# 09-USBUart_PPSMUX_UARTMUX.net
KiCad netlist of a schematic drawn in Altium Designer
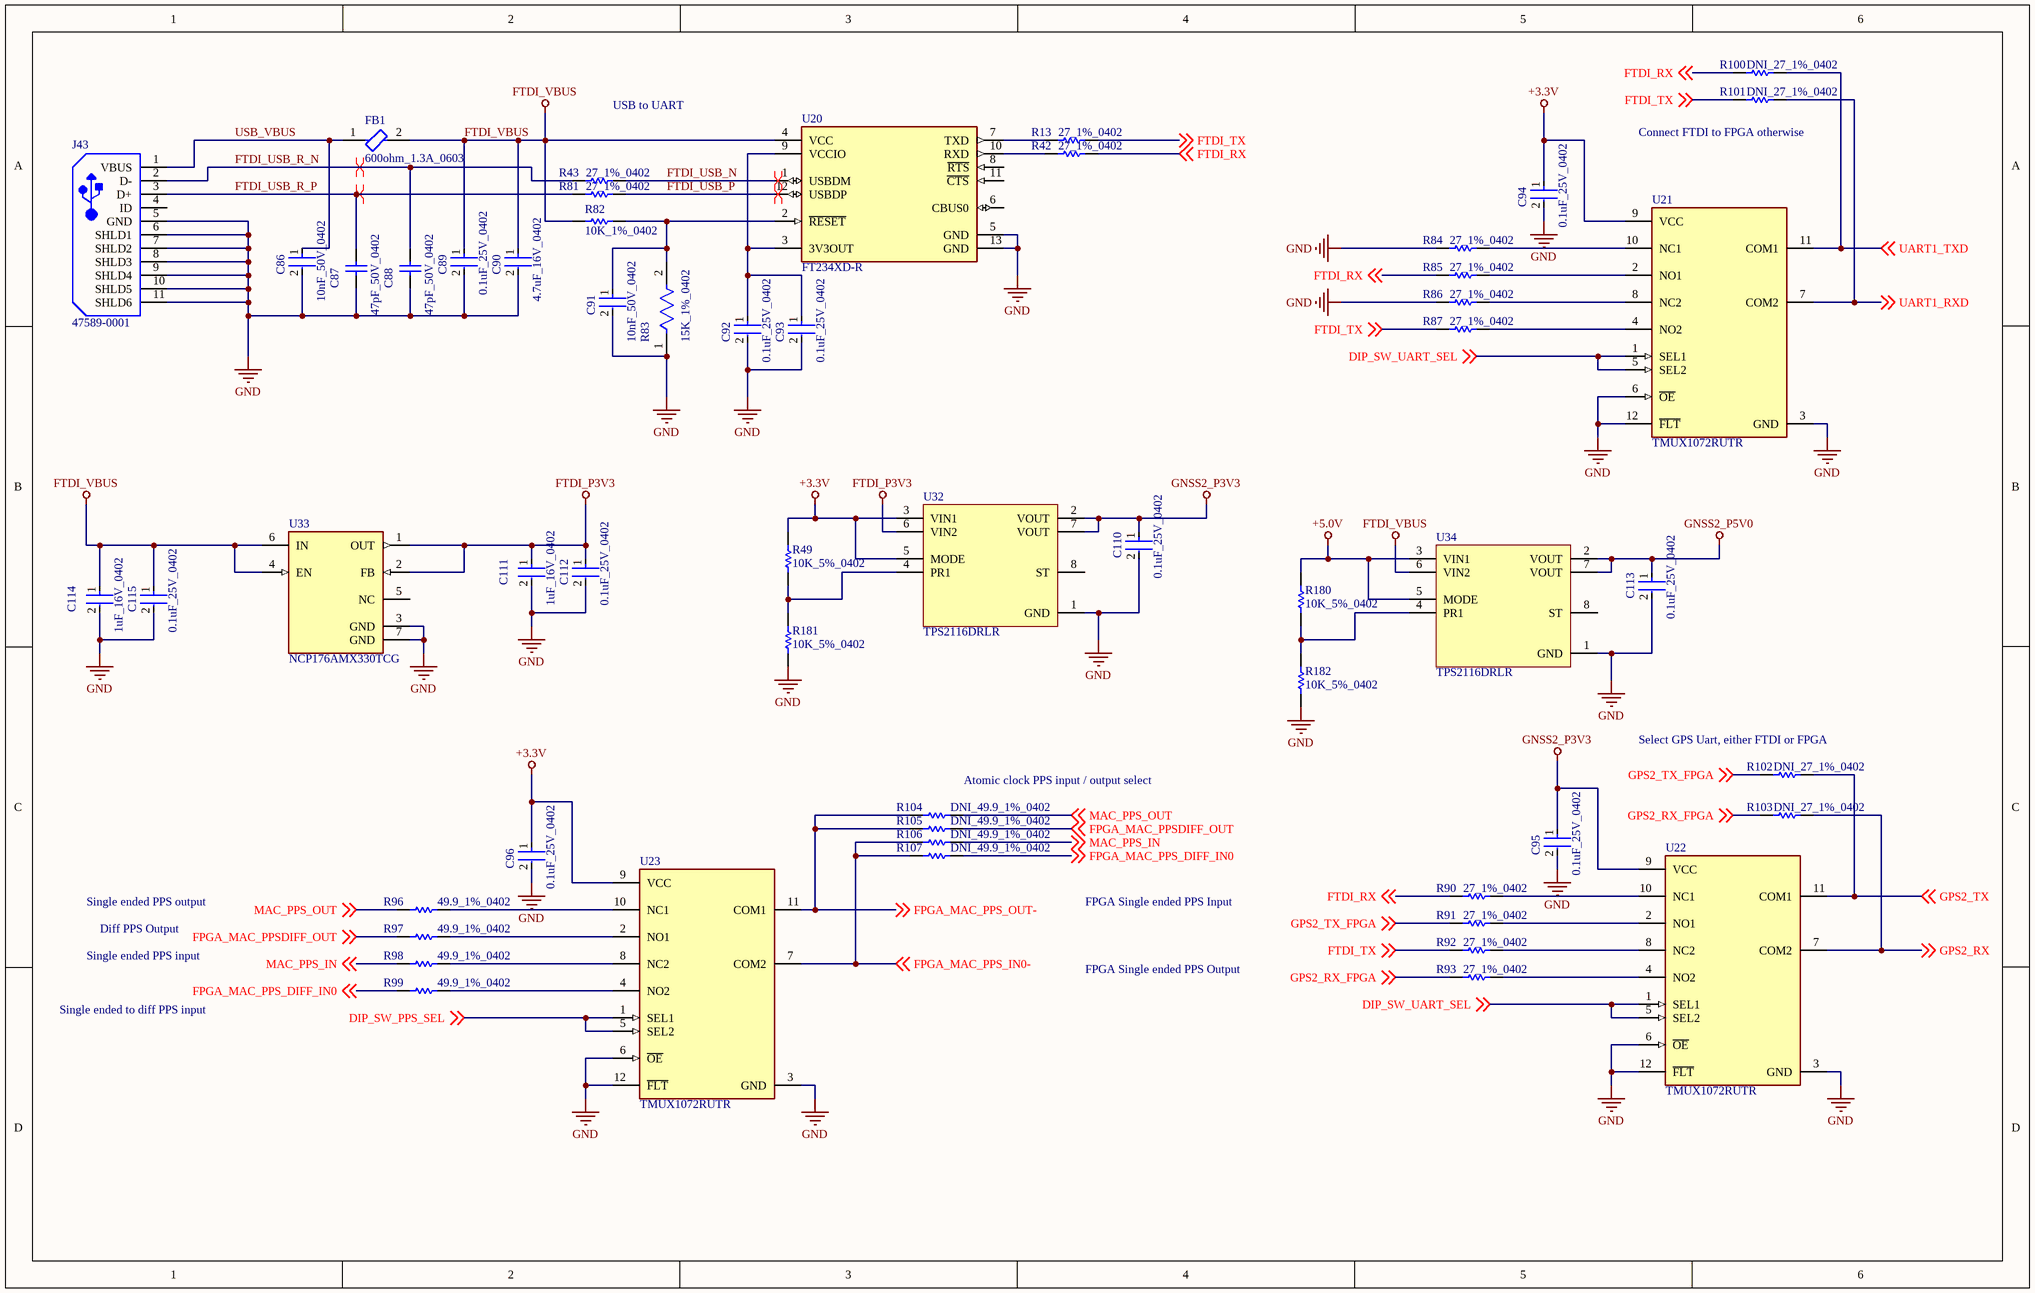
[diagram p0: 09-USBUart_PPSMUX_UARTMUX.SchDoc]

(export (version "E")
  (design (tool "Eeschema 10.0.6"))
  (components
    (comp (ref "C86")
      (value "10nF_50V_0402")
      (footprint "FP-CC0402-MFG")
      (description "CAP CER 10000PF 50V X7R 0402")
      (fields
        (field (name "OCTOPART") "https://octopart.com/cc0402krx7r9bb103-yageo-8376513")
        (field (name "MANUFACTURER PART NUMBER") "CC0402KRX7R9BB103")
      )
      (libsource (lib "Altium Content Vault") (part "11868f565c42a9108669ba33697ecf6"))
    )
    (comp (ref "C87")
      (value "47pF_50V_0402")
      (footprint "CAPC1005X55X25LL05T10")
      (fields (field (name "PART NUMBER") "GRM1555C1H470JA01D") (field (name "MANUFACTURER") "Murata"))
      (libsource (lib "Altium Content Vault") (part "CAP"))
    )
    (comp (ref "C88")
      (value "47pF_50V_0402")
      (footprint "CAPC1005X55X25LL05T10")
      (fields (field (name "PART NUMBER") "GRM1555C1H470JA01D") (field (name "MANUFACTURER") "Murata"))
      (libsource (lib "Altium Content Vault") (part "CAP"))
    )
    (comp (ref "C89")
      (value "0.1uF_25V_0402")
      (footprint "FP-0402-L_1_0_1-W_0_5_0_1-IPC_C")
      (description "General Purpose Ceramic Capacitor, 0402, 100nF, 10%, X7R, 15%, 25V")
      (fields (field (name "VOLTAGE") "25V") (field (name "TOLERANCE") "10%"))
      (libsource (lib "Altium Content Vault") (part "b4654b650e69147ec39a6b967a45e02"))
    )
    (comp (ref "C90")
      (value "4.7uF_16V_0402")
      (footprint "FP-CL829-IPC_C")
      (description "Cap Ceramic 4.7uF 16V X5R ±20% SMD 0402 +85°C Paper T/R")
      (fields (field (name "TOLERANCE") "20%"))
      (libsource (lib "Altium Content Vault") (part "b4654b650e69147ec39a6b967a45e02"))
    )
    (comp (ref "C91")
      (value "10nF_50V_0402")
      (footprint "FP-CC0402-MFG")
      (description "CAP CER 10000PF 50V X7R 0402")
      (fields
        (field (name "OCTOPART") "https://octopart.com/cc0402krx7r9bb103-yageo-8376513")
        (field (name "MANUFACTURER PART NUMBER") "CC0402KRX7R9BB103")
      )
      (libsource (lib "Altium Content Vault") (part "11868f565c42a9108669ba33697ecf6"))
    )
    (comp (ref "C92")
      (value "0.1uF_25V_0402")
      (footprint "FP-0402-L_1_0_1-W_0_5_0_1-IPC_C")
      (description "General Purpose Ceramic Capacitor, 0402, 100nF, 10%, X7R, 15%, 25V")
      (fields (field (name "VOLTAGE") "25V") (field (name "TOLERANCE") "10%"))
      (libsource (lib "Altium Content Vault") (part "b4654b650e69147ec39a6b967a45e02"))
    )
    (comp (ref "C93")
      (value "0.1uF_25V_0402")
      (footprint "FP-0402-L_1_0_1-W_0_5_0_1-IPC_C")
      (description "General Purpose Ceramic Capacitor, 0402, 100nF, 10%, X7R, 15%, 25V")
      (fields (field (name "VOLTAGE") "25V") (field (name "TOLERANCE") "10%"))
      (libsource (lib "Altium Content Vault") (part "b4654b650e69147ec39a6b967a45e02"))
    )
    (comp (ref "C94")
      (value "0.1uF_25V_0402")
      (footprint "FP-0402-L_1_0_1-W_0_5_0_1-IPC_C")
      (description "General Purpose Ceramic Capacitor, 0402, 100nF, 10%, X7R, 15%, 25V")
      (fields (field (name "VOLTAGE") "25V") (field (name "TOLERANCE") "10%"))
      (libsource (lib "Altium Content Vault") (part "b4654b650e69147ec39a6b967a45e02"))
    )
    (comp (ref "C95")
      (value "0.1uF_25V_0402")
      (footprint "FP-0402-L_1_0_1-W_0_5_0_1-IPC_C")
      (description "General Purpose Ceramic Capacitor, 0402, 100nF, 10%, X7R, 15%, 25V")
      (fields (field (name "VOLTAGE") "25V") (field (name "TOLERANCE") "10%"))
      (libsource (lib "Altium Content Vault") (part "b4654b650e69147ec39a6b967a45e02"))
    )
    (comp (ref "C96")
      (value "0.1uF_25V_0402")
      (footprint "FP-0402-L_1_0_1-W_0_5_0_1-IPC_C")
      (description "General Purpose Ceramic Capacitor, 0402, 100nF, 10%, X7R, 15%, 25V")
      (fields (field (name "VOLTAGE") "25V") (field (name "TOLERANCE") "10%"))
      (libsource (lib "Altium Content Vault") (part "b4654b650e69147ec39a6b967a45e02"))
    )
    (comp (ref "C110")
      (value "0.1uF_25V_0402")
      (footprint "FP-0402-L_1_0_1-W_0_5_0_1-IPC_C")
      (description "General Purpose Ceramic Capacitor, 0402, 100nF, 10%, X7R, 15%, 25V")
      (fields (field (name "VOLTAGE") "25V") (field (name "TOLERANCE") "10%"))
      (libsource (lib "Altium Content Vault") (part "b4654b650e69147ec39a6b967a45e02"))
    )
    (comp (ref "C111")
      (value "1uF_16V_0402")
      (footprint "FP-0402-L_1_0_0_05-W_0_5-IPC_A")
      (description "None")
      (fields (field (name "TOLERANCE") "10%"))
      (libsource (lib "Altium Content Vault") (part "b4654b650e69147ec39a6b967a45e02"))
    )
    (comp (ref "C112")
      (value "0.1uF_25V_0402")
      (footprint "FP-0402-L_1_0_1-W_0_5_0_1-IPC_C")
      (description "General Purpose Ceramic Capacitor, 0402, 100nF, 10%, X7R, 15%, 25V")
      (fields (field (name "VOLTAGE") "25V") (field (name "TOLERANCE") "10%"))
      (libsource (lib "Altium Content Vault") (part "b4654b650e69147ec39a6b967a45e02"))
    )
    (comp (ref "C113")
      (value "0.1uF_25V_0402")
      (footprint "FP-0402-L_1_0_1-W_0_5_0_1-IPC_C")
      (description "General Purpose Ceramic Capacitor, 0402, 100nF, 10%, X7R, 15%, 25V")
      (fields (field (name "VOLTAGE") "25V") (field (name "TOLERANCE") "10%"))
      (libsource (lib "Altium Content Vault") (part "b4654b650e69147ec39a6b967a45e02"))
    )
    (comp (ref "C114")
      (value "1uF_16V_0402")
      (footprint "FP-0402-L_1_0_0_05-W_0_5-IPC_A")
      (description "None")
      (fields (field (name "TOLERANCE") "10%"))
      (libsource (lib "Altium Content Vault") (part "b4654b650e69147ec39a6b967a45e02"))
    )
    (comp (ref "C115")
      (value "0.1uF_25V_0402")
      (footprint "FP-0402-L_1_0_1-W_0_5_0_1-IPC_C")
      (description "General Purpose Ceramic Capacitor, 0402, 100nF, 10%, X7R, 15%, 25V")
      (fields (field (name "VOLTAGE") "25V") (field (name "TOLERANCE") "10%"))
      (libsource (lib "Altium Content Vault") (part "b4654b650e69147ec39a6b967a45e02"))
    )
    (comp (ref "FB1")
      (value "600ohm_1.3A_0603")
      (footprint "FP-BLM18-0_15-t0_8-IPC_A")
      (description "Chip Ferrite Bead, 0603, 600Ω @ 100MHz, 0.15Ω, 25%, 1.3A")
      (fields (field (name "TOLERANCE") "25%"))
      (libsource (lib "Altium Content Vault") (part "5f30dd21d616792df468990f7003faa"))
    )
    (comp (ref "J43")
      (value "47589-0001")
      (footprint "MOLX-47589-0001_V")
      (description "Right Angle Female Type AB Micro USB Connector, 30 V, 1.8 A, -30 to 85 degC, RoHS, Tape and Reel")
      (fields (field (name "MANUFACTURER") "Molex"))
      (libsource (lib "Altium Content Vault") (part "USB-5-6SHLD"))
    )
    (comp (ref "R13")
      (value "27_1%_0402")
      (footprint "RESC1005X40X25NL05T05")
      (fields (field (name "PART NUMBER") "CRCW040227R0FKED") (field (name "MANUFACTURER") "Vishay Dale"))
      (libsource (lib "Altium Content Vault") (part "RES"))
    )
    (comp (ref "R42")
      (value "27_1%_0402")
      (footprint "RESC1005X40X25NL05T05")
      (fields (field (name "PART NUMBER") "CRCW040227R0FKED") (field (name "MANUFACTURER") "Vishay Dale"))
      (libsource (lib "Altium Content Vault") (part "RES"))
    )
    (comp (ref "R43")
      (value "27_1%_0402")
      (footprint "RESC1005X40X25NL05T05")
      (fields (field (name "PART NUMBER") "CRCW040227R0FKED") (field (name "MANUFACTURER") "Vishay Dale"))
      (libsource (lib "Altium Content Vault") (part "RES"))
    )
    (comp (ref "R49")
      (value "10K_5%_0402")
      (footprint "RESC1005X40X25ML05T05")
      (fields (field (name "PART NUMBER") "ERJ-2GEJ103X") (field (name "MANUFACTURER") "Panasonic"))
      (libsource (lib "Altium Content Vault") (part "RES"))
    )
    (comp (ref "R81")
      (value "27_1%_0402")
      (footprint "RESC1005X40X25NL05T05")
      (fields (field (name "PART NUMBER") "CRCW040227R0FKED") (field (name "MANUFACTURER") "Vishay Dale"))
      (libsource (lib "Altium Content Vault") (part "RES"))
    )
    (comp (ref "R82")
      (value "10K_1%_0402")
      (footprint "RESC1005X40X25LL05T10")
      (fields (field (name "PART NUMBER") "RC0402FR-0710KL") (field (name "MANUFACTURER") "Yageo / Phycomp"))
      (libsource (lib "Altium Content Vault") (part "RES"))
    )
    (comp (ref "R83")
      (value "15K_1%_0402")
      (footprint "FP-ERJ2R-MFG")
      (description "RES SMD 15K OHM 1% 1/10W 0402")
      (fields (field (name "TOLERANCE") "1%") (field (name "MANUFACTURER PART NUMBER") "ERJ-2RKF1502X"))
      (libsource (lib "Altium Content Vault") (part "1029c3af85768c4190bb7ad29bc67b5"))
    )
    (comp (ref "R84")
      (value "27_1%_0402")
      (footprint "RESC1005X40X25NL05T05")
      (fields (field (name "PART NUMBER") "CRCW040227R0FKED") (field (name "MANUFACTURER") "Vishay Dale"))
      (libsource (lib "Altium Content Vault") (part "RES"))
    )
    (comp (ref "R85")
      (value "27_1%_0402")
      (footprint "RESC1005X40X25NL05T05")
      (fields (field (name "PART NUMBER") "CRCW040227R0FKED") (field (name "MANUFACTURER") "Vishay Dale"))
      (libsource (lib "Altium Content Vault") (part "RES"))
    )
    (comp (ref "R86")
      (value "27_1%_0402")
      (footprint "RESC1005X40X25NL05T05")
      (fields (field (name "PART NUMBER") "CRCW040227R0FKED") (field (name "MANUFACTURER") "Vishay Dale"))
      (libsource (lib "Altium Content Vault") (part "RES"))
    )
    (comp (ref "R87")
      (value "27_1%_0402")
      (footprint "RESC1005X40X25NL05T05")
      (fields (field (name "PART NUMBER") "CRCW040227R0FKED") (field (name "MANUFACTURER") "Vishay Dale"))
      (libsource (lib "Altium Content Vault") (part "RES"))
    )
    (comp (ref "R90")
      (value "27_1%_0402")
      (footprint "RESC1005X40X25NL05T05")
      (fields (field (name "PART NUMBER") "CRCW040227R0FKED") (field (name "MANUFACTURER") "Vishay Dale"))
      (libsource (lib "Altium Content Vault") (part "RES"))
    )
    (comp (ref "R91")
      (value "27_1%_0402")
      (footprint "RESC1005X40X25NL05T05")
      (fields (field (name "PART NUMBER") "CRCW040227R0FKED") (field (name "MANUFACTURER") "Vishay Dale"))
      (libsource (lib "Altium Content Vault") (part "RES"))
    )
    (comp (ref "R92")
      (value "27_1%_0402")
      (footprint "RESC1005X40X25NL05T05")
      (fields (field (name "PART NUMBER") "CRCW040227R0FKED") (field (name "MANUFACTURER") "Vishay Dale"))
      (libsource (lib "Altium Content Vault") (part "RES"))
    )
    (comp (ref "R93")
      (value "27_1%_0402")
      (footprint "RESC1005X40X25NL05T05")
      (fields (field (name "PART NUMBER") "CRCW040227R0FKED") (field (name "MANUFACTURER") "Vishay Dale"))
      (libsource (lib "Altium Content Vault") (part "RES"))
    )
    (comp (ref "R96")
      (value "49.9_1%_0402")
      (footprint "RESC1005X40X25LL05T10")
      (fields (field (name "MANUFACTURER") "Yageo / Phycomp") (field (name "PART NUMBER") "RC0402FR-0749R9L"))
      (libsource (lib "Altium Content Vault") (part "RES"))
    )
    (comp (ref "R97")
      (value "49.9_1%_0402")
      (footprint "RESC1005X40X25LL05T10")
      (fields (field (name "MANUFACTURER") "Yageo / Phycomp") (field (name "PART NUMBER") "RC0402FR-0749R9L"))
      (libsource (lib "Altium Content Vault") (part "RES"))
    )
    (comp (ref "R98")
      (value "49.9_1%_0402")
      (footprint "RESC1005X40X25LL05T10")
      (fields (field (name "MANUFACTURER") "Yageo / Phycomp") (field (name "PART NUMBER") "RC0402FR-0749R9L"))
      (libsource (lib "Altium Content Vault") (part "RES"))
    )
    (comp (ref "R99")
      (value "49.9_1%_0402")
      (footprint "RESC1005X40X25LL05T10")
      (fields (field (name "MANUFACTURER") "Yageo / Phycomp") (field (name "PART NUMBER") "RC0402FR-0749R9L"))
      (libsource (lib "Altium Content Vault") (part "RES"))
    )
    (comp (ref "R100")
      (value "DNI_27_1%_0402")
      (footprint "RESC1005X40X25NL05T05")
      (fields (field (name "PART NUMBER") "CRCW040227R0FKED") (field (name "MANUFACTURER") "Vishay Dale"))
      (libsource (lib "Altium Content Vault") (part "RES"))
    )
    (comp (ref "R101")
      (value "DNI_27_1%_0402")
      (footprint "RESC1005X40X25NL05T05")
      (fields (field (name "PART NUMBER") "CRCW040227R0FKED") (field (name "MANUFACTURER") "Vishay Dale"))
      (libsource (lib "Altium Content Vault") (part "RES"))
    )
    (comp (ref "R102")
      (value "DNI_27_1%_0402")
      (footprint "RESC1005X40X25NL05T05")
      (fields (field (name "PART NUMBER") "CRCW040227R0FKED") (field (name "MANUFACTURER") "Vishay Dale"))
      (libsource (lib "Altium Content Vault") (part "RES"))
    )
    (comp (ref "R103")
      (value "DNI_27_1%_0402")
      (footprint "RESC1005X40X25NL05T05")
      (fields (field (name "PART NUMBER") "CRCW040227R0FKED") (field (name "MANUFACTURER") "Vishay Dale"))
      (libsource (lib "Altium Content Vault") (part "RES"))
    )
    (comp (ref "R104")
      (value "DNI_49.9_1%_0402")
      (footprint "RESC1005X40X25LL05T10")
      (fields (field (name "MANUFACTURER") "Yageo / Phycomp") (field (name "PART NUMBER") "RC0402FR-0749R9L"))
      (libsource (lib "Altium Content Vault") (part "RES"))
    )
    (comp (ref "R105")
      (value "DNI_49.9_1%_0402")
      (footprint "RESC1005X40X25LL05T10")
      (fields (field (name "MANUFACTURER") "Yageo / Phycomp") (field (name "PART NUMBER") "RC0402FR-0749R9L"))
      (libsource (lib "Altium Content Vault") (part "RES"))
    )
    (comp (ref "R106")
      (value "DNI_49.9_1%_0402")
      (footprint "RESC1005X40X25LL05T10")
      (fields (field (name "MANUFACTURER") "Yageo / Phycomp") (field (name "PART NUMBER") "RC0402FR-0749R9L"))
      (libsource (lib "Altium Content Vault") (part "RES"))
    )
    (comp (ref "R107")
      (value "DNI_49.9_1%_0402")
      (footprint "RESC1005X40X25LL05T10")
      (fields (field (name "MANUFACTURER") "Yageo / Phycomp") (field (name "PART NUMBER") "RC0402FR-0749R9L"))
      (libsource (lib "Altium Content Vault") (part "RES"))
    )
    (comp (ref "R180")
      (value "10K_5%_0402")
      (footprint "RESC1005X40X25ML05T05")
      (fields (field (name "PART NUMBER") "ERJ-2GEJ103X") (field (name "MANUFACTURER") "Panasonic"))
      (libsource (lib "Altium Content Vault") (part "RES"))
    )
    (comp (ref "R181")
      (value "10K_5%_0402")
      (footprint "RESC1005X40X25ML05T05")
      (fields (field (name "PART NUMBER") "ERJ-2GEJ103X") (field (name "MANUFACTURER") "Panasonic"))
      (libsource (lib "Altium Content Vault") (part "RES"))
    )
    (comp (ref "R182")
      (value "10K_5%_0402")
      (footprint "RESC1005X40X25ML05T05")
      (fields (field (name "PART NUMBER") "ERJ-2GEJ103X") (field (name "MANUFACTURER") "Panasonic"))
      (libsource (lib "Altium Content Vault") (part "RES"))
    )
    (comp (ref "U20")
      (value "FT234XD-R")
      (footprint "FP-DFN-12-IPC_B")
      (description "IC USB SERIAL BASIC UART 12DFN")
      (libsource (lib "Altium Content Vault") (part "4bef3367ed9f9051bcb84ab46edda1c"))
    )
    (comp (ref "U21")
      (value "TMUX1072RUTR")
      (footprint "FP-RUT0012A-MFG")
      (description "IC SWITCH SPDT DUAL 12UQFN")
      (libsource (lib "Altium Content Vault") (part "12a319ab100cd6cfe745e35972674f5"))
    )
    (comp (ref "U22")
      (value "TMUX1072RUTR")
      (footprint "FP-RUT0012A-MFG")
      (description "IC SWITCH SPDT DUAL 12UQFN")
      (libsource (lib "Altium Content Vault") (part "12a319ab100cd6cfe745e35972674f5"))
    )
    (comp (ref "U23")
      (value "TMUX1072RUTR")
      (footprint "FP-RUT0012A-MFG")
      (description "IC SWITCH SPDT DUAL 12UQFN")
      (libsource (lib "Altium Content Vault") (part "12a319ab100cd6cfe745e35972674f5"))
    )
    (comp (ref "U32")
      (value "TPS2116DRLR")
      (footprint "IC_TPS2116")
      (description "1.6-V to 5.5-V, 40-mΩ, 2.5-A, low-IQ, priority power multiplexer 8-SOT-5X3 -40 to 125")
      (fields (field (name "MF") "Texas Instruments"))
      (libsource (lib "LotusSound") (part "IC_TPS2116DRLR"))
    )
    (comp (ref "U33")
      (value "NCP176AMX330TCG")
      (footprint "FP-711AT-MFG")
      (description "IC REG LINEAR 3.3V 500MA 6XDFN")
      (fields
        (field (name "MANUFACTURER") "ON Semiconductor")
        (field (name "OCTOPART") "https://octopart.com/ncp176amx330tcg-on+semiconductor-61522616")
      )
      (libsource (lib "Altium Content Vault") (part "a38d0f79c2a9f01c07a7e52882ed186"))
    )
    (comp (ref "U34")
      (value "TPS2116DRLR")
      (footprint "IC_TPS2116")
      (description "1.6-V to 5.5-V, 40-mΩ, 2.5-A, low-IQ, priority power multiplexer 8-SOT-5X3 -40 to 125")
      (fields (field (name "MF") "Texas Instruments"))
      (libsource (lib "LotusSound") (part "IC_TPS2116DRLR"))
    )
  )
  (nets
    (net (code "1") (name "+3.3V") (class "Default")
      (node (ref "C94") (pin "1") (pinfunction "1_1") (pintype "passive"))
      (node (ref "C96") (pin "1") (pinfunction "1_1") (pintype "passive"))
      (node (ref "R49") (pin "2") (pinfunction "2_2") (pintype "passive"))
      (node (ref "U21") (pin "9") (pinfunction "VCC_9") (pintype "power_in"))
      (node (ref "U23") (pin "9") (pinfunction "VCC_9") (pintype "power_in"))
      (node (ref "U32") (pin "3") (pinfunction "VIN1_3") (pintype "passive"))
      (node (ref "U32") (pin "5") (pinfunction "MODE_5") (pintype "passive"))
    )
    (net (code "2") (name "+5.0V") (class "Default")
      (node (ref "R180") (pin "2") (pinfunction "2_2") (pintype "passive"))
      (node (ref "U34") (pin "3") (pinfunction "VIN1_3") (pintype "passive"))
      (node (ref "U34") (pin "5") (pinfunction "MODE_5") (pintype "passive"))
    )
    (net (code "3") (name "/FTDI_USB_N") (class "Default")
      (node (ref "R43") (pin "2") (pinfunction "2_2") (pintype "passive"))
      (node (ref "U20") (pin "1") (pinfunction "USBDM_1") (pintype "bidirectional"))
    )
    (net (code "4") (name "/FTDI_USB_P") (class "Default")
      (node (ref "R81") (pin "2") (pinfunction "2_2") (pintype "passive"))
      (node (ref "U20") (pin "12") (pinfunction "USBDP_12") (pintype "bidirectional"))
    )
    (net (code "5") (name "/FTDI_USB_R_N") (class "Default")
      (node (ref "C88") (pin "2") (pinfunction "2_2") (pintype "passive"))
      (node (ref "J43") (pin "2") (pinfunction "D-_2") (pintype "passive"))
      (node (ref "R43") (pin "1") (pinfunction "1_1") (pintype "passive"))
    )
    (net (code "6") (name "/FTDI_USB_R_P") (class "Default")
      (node (ref "C87") (pin "2") (pinfunction "2_2") (pintype "passive"))
      (node (ref "J43") (pin "3") (pinfunction "D+_3") (pintype "passive"))
      (node (ref "R81") (pin "1") (pinfunction "1_1") (pintype "passive"))
    )
    (net (code "7") (name "/USB_VBUS") (class "Default")
      (node (ref "C86") (pin "1") (pinfunction "1_1") (pintype "passive"))
      (node (ref "FB1") (pin "1") (pinfunction "1_1") (pintype "passive"))
      (node (ref "J43") (pin "1") (pinfunction "VBUS_1") (pintype "passive"))
    )
    (net (code "8") (name "DIP_SW_PPS_SEL") (class "Default")
      (node (ref "U23") (pin "1") (pinfunction "SEL1_1") (pintype "input"))
      (node (ref "U23") (pin "5") (pinfunction "SEL2_5") (pintype "input"))
    )
    (net (code "9") (name "DIP_SW_UART_SEL") (class "Default")
      (node (ref "U21") (pin "1") (pinfunction "SEL1_1") (pintype "input"))
      (node (ref "U21") (pin "5") (pinfunction "SEL2_5") (pintype "input"))
      (node (ref "U22") (pin "1") (pinfunction "SEL1_1") (pintype "input"))
      (node (ref "U22") (pin "5") (pinfunction "SEL2_5") (pintype "input"))
    )
    (net (code "10") (name "FPGA_MAC_PPSDIFF_OUT") (class "Default")
      (node (ref "R105") (pin "2") (pinfunction "2_2") (pintype "passive"))
      (node (ref "R97") (pin "1") (pinfunction "1_1") (pintype "passive"))
    )
    (net (code "11") (name "FPGA_MAC_PPS_DIFF_IN0") (class "Default")
      (node (ref "R107") (pin "2") (pinfunction "2_2") (pintype "passive"))
      (node (ref "R99") (pin "1") (pinfunction "1_1") (pintype "passive"))
    )
    (net (code "12") (name "FPGA_MAC_PPS_IN0-") (class "Default")
      (node (ref "R106") (pin "1") (pinfunction "1_1") (pintype "passive"))
      (node (ref "R107") (pin "1") (pinfunction "1_1") (pintype "passive"))
      (node (ref "U23") (pin "7") (pinfunction "COM2_7") (pintype "passive"))
    )
    (net (code "13") (name "FPGA_MAC_PPS_OUT-") (class "Default")
      (node (ref "R104") (pin "1") (pinfunction "1_1") (pintype "passive"))
      (node (ref "R105") (pin "1") (pinfunction "1_1") (pintype "passive"))
      (node (ref "U23") (pin "11") (pinfunction "COM1_11") (pintype "passive"))
    )
    (net (code "14") (name "FTDI_P3V3") (class "Default")
      (node (ref "C111") (pin "1") (pinfunction "1_1") (pintype "passive"))
      (node (ref "C112") (pin "1") (pinfunction "1_1") (pintype "passive"))
      (node (ref "U32") (pin "6") (pinfunction "VIN2_6") (pintype "passive"))
      (node (ref "U33") (pin "1") (pinfunction "OUT_1") (pintype "output"))
      (node (ref "U33") (pin "2") (pinfunction "FB_2") (pintype "input"))
    )
    (net (code "15") (name "FTDI_RX") (class "Default")
      (node (ref "R100") (pin "1") (pinfunction "1_1") (pintype "passive"))
      (node (ref "R42") (pin "2") (pinfunction "2_2") (pintype "passive"))
      (node (ref "R85") (pin "1") (pinfunction "1_1") (pintype "passive"))
      (node (ref "R90") (pin "1") (pinfunction "1_1") (pintype "passive"))
    )
    (net (code "16") (name "FTDI_TX") (class "Default")
      (node (ref "R101") (pin "1") (pinfunction "1_1") (pintype "passive"))
      (node (ref "R13") (pin "2") (pinfunction "2_2") (pintype "passive"))
      (node (ref "R87") (pin "1") (pinfunction "1_1") (pintype "passive"))
      (node (ref "R92") (pin "1") (pinfunction "1_1") (pintype "passive"))
    )
    (net (code "17") (name "FTDI_VBUS") (class "Default")
      (node (ref "C114") (pin "1") (pinfunction "1_1") (pintype "passive"))
      (node (ref "C115") (pin "1") (pinfunction "1_1") (pintype "passive"))
      (node (ref "C89") (pin "1") (pinfunction "1_1") (pintype "passive"))
      (node (ref "C90") (pin "1") (pinfunction "1_1") (pintype "passive"))
      (node (ref "FB1") (pin "2") (pinfunction "2_2") (pintype "passive"))
      (node (ref "R82") (pin "2") (pinfunction "2_2") (pintype "passive"))
      (node (ref "U20") (pin "4") (pinfunction "VCC_4") (pintype "power_in"))
      (node (ref "U33") (pin "4") (pinfunction "EN_4") (pintype "input"))
      (node (ref "U33") (pin "6") (pinfunction "IN_6") (pintype "power_in"))
      (node (ref "U34") (pin "6") (pinfunction "VIN2_6") (pintype "passive"))
    )
    (net (code "18") (name "GND") (class "Default")
      (node (ref "C110") (pin "2") (pinfunction "2_2") (pintype "passive"))
      (node (ref "C111") (pin "2") (pinfunction "2_2") (pintype "passive"))
      (node (ref "C112") (pin "2") (pinfunction "2_2") (pintype "passive"))
      (node (ref "C113") (pin "2") (pinfunction "2_2") (pintype "passive"))
      (node (ref "C114") (pin "2") (pinfunction "2_2") (pintype "passive"))
      (node (ref "C115") (pin "2") (pinfunction "2_2") (pintype "passive"))
      (node (ref "C86") (pin "2") (pinfunction "2_2") (pintype "passive"))
      (node (ref "C87") (pin "1") (pinfunction "1_1") (pintype "passive"))
      (node (ref "C88") (pin "1") (pinfunction "1_1") (pintype "passive"))
      (node (ref "C89") (pin "2") (pinfunction "2_2") (pintype "passive"))
      (node (ref "C90") (pin "2") (pinfunction "2_2") (pintype "passive"))
      (node (ref "C91") (pin "2") (pinfunction "2_2") (pintype "passive"))
      (node (ref "C92") (pin "2") (pinfunction "2_2") (pintype "passive"))
      (node (ref "C93") (pin "2") (pinfunction "2_2") (pintype "passive"))
      (node (ref "C94") (pin "2") (pinfunction "2_2") (pintype "passive"))
      (node (ref "C95") (pin "2") (pinfunction "2_2") (pintype "passive"))
      (node (ref "C96") (pin "2") (pinfunction "2_2") (pintype "passive"))
      (node (ref "J43") (pin "10") (pinfunction "SHLD5_10") (pintype "passive"))
      (node (ref "J43") (pin "11") (pinfunction "SHLD6_11") (pintype "passive"))
      (node (ref "J43") (pin "5") (pinfunction "GND_5") (pintype "passive"))
      (node (ref "J43") (pin "6") (pinfunction "SHLD1_6") (pintype "passive"))
      (node (ref "J43") (pin "7") (pinfunction "SHLD2_7") (pintype "passive"))
      (node (ref "J43") (pin "8") (pinfunction "SHLD3_8") (pintype "passive"))
      (node (ref "J43") (pin "9") (pinfunction "SHLD4_9") (pintype "passive"))
      (node (ref "R181") (pin "1") (pinfunction "1_1") (pintype "passive"))
      (node (ref "R182") (pin "1") (pinfunction "1_1") (pintype "passive"))
      (node (ref "R83") (pin "1") (pinfunction "1_1") (pintype "passive"))
      (node (ref "R84") (pin "1") (pinfunction "1_1") (pintype "passive"))
      (node (ref "R86") (pin "1") (pinfunction "1_1") (pintype "passive"))
      (node (ref "U20") (pin "13") (pinfunction "GND_13") (pintype "power_in"))
      (node (ref "U20") (pin "5") (pinfunction "GND_5") (pintype "power_in"))
      (node (ref "U21") (pin "12") (pinfunction "~{FLT}_12") (pintype "open_collector"))
      (node (ref "U21") (pin "3") (pinfunction "GND_3") (pintype "power_in"))
      (node (ref "U21") (pin "6") (pinfunction "~{OE}_6") (pintype "input"))
      (node (ref "U22") (pin "12") (pinfunction "~{FLT}_12") (pintype "open_collector"))
      (node (ref "U22") (pin "3") (pinfunction "GND_3") (pintype "power_in"))
      (node (ref "U22") (pin "6") (pinfunction "~{OE}_6") (pintype "input"))
      (node (ref "U23") (pin "12") (pinfunction "~{FLT}_12") (pintype "open_collector"))
      (node (ref "U23") (pin "3") (pinfunction "GND_3") (pintype "power_in"))
      (node (ref "U23") (pin "6") (pinfunction "~{OE}_6") (pintype "input"))
      (node (ref "U32") (pin "1") (pinfunction "GND_1") (pintype "passive"))
      (node (ref "U33") (pin "3") (pinfunction "GND_3") (pintype "power_in"))
      (node (ref "U33") (pin "7") (pinfunction "GND_7") (pintype "power_in"))
      (node (ref "U34") (pin "1") (pinfunction "GND_1") (pintype "passive"))
    )
    (net (code "19") (name "GNSS2_P3V3") (class "Default")
      (node (ref "C110") (pin "1") (pinfunction "1_1") (pintype "passive"))
      (node (ref "C95") (pin "1") (pinfunction "1_1") (pintype "passive"))
      (node (ref "U22") (pin "9") (pinfunction "VCC_9") (pintype "power_in"))
      (node (ref "U32") (pin "2") (pinfunction "VOUT_2") (pintype "passive"))
      (node (ref "U32") (pin "7") (pinfunction "VOUT_7") (pintype "passive"))
    )
    (net (code "20") (name "GNSS2_P5V0") (class "Default")
      (node (ref "C113") (pin "1") (pinfunction "1_1") (pintype "passive"))
      (node (ref "U34") (pin "2") (pinfunction "VOUT_2") (pintype "passive"))
      (node (ref "U34") (pin "7") (pinfunction "VOUT_7") (pintype "passive"))
    )
    (net (code "21") (name "GPS2_RX") (class "Default")
      (node (ref "R103") (pin "2") (pinfunction "2_2") (pintype "passive"))
      (node (ref "U22") (pin "7") (pinfunction "COM2_7") (pintype "passive"))
    )
    (net (code "22") (name "GPS2_RX_FPGA") (class "Default")
      (node (ref "R103") (pin "1") (pinfunction "1_1") (pintype "passive"))
      (node (ref "R93") (pin "1") (pinfunction "1_1") (pintype "passive"))
    )
    (net (code "23") (name "GPS2_TX") (class "Default")
      (node (ref "R102") (pin "2") (pinfunction "2_2") (pintype "passive"))
      (node (ref "U22") (pin "11") (pinfunction "COM1_11") (pintype "passive"))
    )
    (net (code "24") (name "GPS2_TX_FPGA") (class "Default")
      (node (ref "R102") (pin "1") (pinfunction "1_1") (pintype "passive"))
      (node (ref "R91") (pin "1") (pinfunction "1_1") (pintype "passive"))
    )
    (net (code "25") (name "MAC_PPS_IN") (class "Default")
      (node (ref "R106") (pin "2") (pinfunction "2_2") (pintype "passive"))
      (node (ref "R98") (pin "1") (pinfunction "1_1") (pintype "passive"))
    )
    (net (code "26") (name "MAC_PPS_OUT") (class "Default")
      (node (ref "R104") (pin "2") (pinfunction "2_2") (pintype "passive"))
      (node (ref "R96") (pin "1") (pinfunction "1_1") (pintype "passive"))
    )
    (net (code "27") (name "Net-(U20-3V3OUT)") (class "Default")
      (node (ref "C92") (pin "1") (pinfunction "1_1") (pintype "passive"))
      (node (ref "C93") (pin "1") (pinfunction "1_1") (pintype "passive"))
      (node (ref "U20") (pin "3") (pinfunction "3V3OUT_3") (pintype "power_in"))
      (node (ref "U20") (pin "9") (pinfunction "VCCIO_9") (pintype "power_in"))
    )
    (net (code "28") (name "Net-(U20-RXD)") (class "Default")
      (node (ref "R42") (pin "1") (pinfunction "1_1") (pintype "passive"))
      (node (ref "U20") (pin "10") (pinfunction "RXD_10") (pintype "output"))
    )
    (net (code "29") (name "Net-(U20-TXD)") (class "Default")
      (node (ref "R13") (pin "1") (pinfunction "1_1") (pintype "passive"))
      (node (ref "U20") (pin "7") (pinfunction "TXD_7") (pintype "output"))
    )
    (net (code "30") (name "Net-(U20-~{RESET})") (class "Default")
      (node (ref "C91") (pin "1") (pinfunction "1_1") (pintype "passive"))
      (node (ref "R82") (pin "1") (pinfunction "1_1") (pintype "passive"))
      (node (ref "R83") (pin "2") (pinfunction "2_2") (pintype "passive"))
      (node (ref "U20") (pin "2") (pinfunction "~{RESET}_2") (pintype "input"))
    )
    (net (code "31") (name "Net-(U21-NC1)") (class "Default")
      (node (ref "R84") (pin "2") (pinfunction "2_2") (pintype "passive"))
      (node (ref "U21") (pin "10") (pinfunction "NC1_10") (pintype "passive"))
    )
    (net (code "32") (name "Net-(U21-NC2)") (class "Default")
      (node (ref "R86") (pin "2") (pinfunction "2_2") (pintype "passive"))
      (node (ref "U21") (pin "8") (pinfunction "NC2_8") (pintype "passive"))
    )
    (net (code "33") (name "Net-(U21-NO1)") (class "Default")
      (node (ref "R85") (pin "2") (pinfunction "2_2") (pintype "passive"))
      (node (ref "U21") (pin "2") (pinfunction "NO1_2") (pintype "passive"))
    )
    (net (code "34") (name "Net-(U21-NO2)") (class "Default")
      (node (ref "R87") (pin "2") (pinfunction "2_2") (pintype "passive"))
      (node (ref "U21") (pin "4") (pinfunction "NO2_4") (pintype "passive"))
    )
    (net (code "35") (name "Net-(U22-NC1)") (class "Default")
      (node (ref "R90") (pin "2") (pinfunction "2_2") (pintype "passive"))
      (node (ref "U22") (pin "10") (pinfunction "NC1_10") (pintype "passive"))
    )
    (net (code "36") (name "Net-(U22-NC2)") (class "Default")
      (node (ref "R92") (pin "2") (pinfunction "2_2") (pintype "passive"))
      (node (ref "U22") (pin "8") (pinfunction "NC2_8") (pintype "passive"))
    )
    (net (code "37") (name "Net-(U22-NO1)") (class "Default")
      (node (ref "R91") (pin "2") (pinfunction "2_2") (pintype "passive"))
      (node (ref "U22") (pin "2") (pinfunction "NO1_2") (pintype "passive"))
    )
    (net (code "38") (name "Net-(U22-NO2)") (class "Default")
      (node (ref "R93") (pin "2") (pinfunction "2_2") (pintype "passive"))
      (node (ref "U22") (pin "4") (pinfunction "NO2_4") (pintype "passive"))
    )
    (net (code "39") (name "Net-(U23-NC1)") (class "Default")
      (node (ref "R96") (pin "2") (pinfunction "2_2") (pintype "passive"))
      (node (ref "U23") (pin "10") (pinfunction "NC1_10") (pintype "passive"))
    )
    (net (code "40") (name "Net-(U23-NC2)") (class "Default")
      (node (ref "R98") (pin "2") (pinfunction "2_2") (pintype "passive"))
      (node (ref "U23") (pin "8") (pinfunction "NC2_8") (pintype "passive"))
    )
    (net (code "41") (name "Net-(U23-NO1)") (class "Default")
      (node (ref "R97") (pin "2") (pinfunction "2_2") (pintype "passive"))
      (node (ref "U23") (pin "2") (pinfunction "NO1_2") (pintype "passive"))
    )
    (net (code "42") (name "Net-(U23-NO2)") (class "Default")
      (node (ref "R99") (pin "2") (pinfunction "2_2") (pintype "passive"))
      (node (ref "U23") (pin "4") (pinfunction "NO2_4") (pintype "passive"))
    )
    (net (code "43") (name "Net-(U32-PR1)") (class "Default")
      (node (ref "R181") (pin "2") (pinfunction "2_2") (pintype "passive"))
      (node (ref "R49") (pin "1") (pinfunction "1_1") (pintype "passive"))
      (node (ref "U32") (pin "4") (pinfunction "PR1_4") (pintype "passive"))
    )
    (net (code "44") (name "Net-(U34-PR1)") (class "Default")
      (node (ref "R180") (pin "1") (pinfunction "1_1") (pintype "passive"))
      (node (ref "R182") (pin "2") (pinfunction "2_2") (pintype "passive"))
      (node (ref "U34") (pin "4") (pinfunction "PR1_4") (pintype "passive"))
    )
    (net (code "45") (name "UART1_RXD") (class "Default")
      (node (ref "R101") (pin "2") (pinfunction "2_2") (pintype "passive"))
      (node (ref "U21") (pin "7") (pinfunction "COM2_7") (pintype "passive"))
    )
    (net (code "46") (name "UART1_TXD") (class "Default")
      (node (ref "R100") (pin "2") (pinfunction "2_2") (pintype "passive"))
      (node (ref "U21") (pin "11") (pinfunction "COM1_11") (pintype "passive"))
    )
    (net (code "47") (name "unconnected-(J43-ID-Pad4)") (class "Default")
      (node (ref "J43") (pin "4") (pinfunction "ID_4") (pintype "passive"))
    )
    (net (code "48") (name "unconnected-(U20-CBUS0-Pad6)") (class "Default")
      (node (ref "U20") (pin "6") (pinfunction "CBUS0_6") (pintype "bidirectional"))
    )
    (net (code "49") (name "unconnected-(U20-~{CTS}-Pad11)") (class "Default")
      (node (ref "U20") (pin "11") (pinfunction "~{CTS}_11") (pintype "input"))
    )
    (net (code "50") (name "unconnected-(U20-~{RTS}-Pad8)") (class "Default")
      (node (ref "U20") (pin "8") (pinfunction "~{RTS}_8") (pintype "input"))
    )
    (net (code "51") (name "unconnected-(U32-ST-Pad8)") (class "Default")
      (node (ref "U32") (pin "8") (pinfunction "ST_8") (pintype "passive"))
    )
    (net (code "52") (name "unconnected-(U33-NC-Pad5)") (class "Default")
      (node (ref "U33") (pin "5") (pinfunction "NC_5") (pintype "passive"))
    )
    (net (code "53") (name "unconnected-(U34-ST-Pad8)") (class "Default")
      (node (ref "U34") (pin "8") (pinfunction "ST_8") (pintype "passive"))
    )
  )
)
